# le_grand_strum.net
KiCad netlist of a schematic drawn in EAGLE
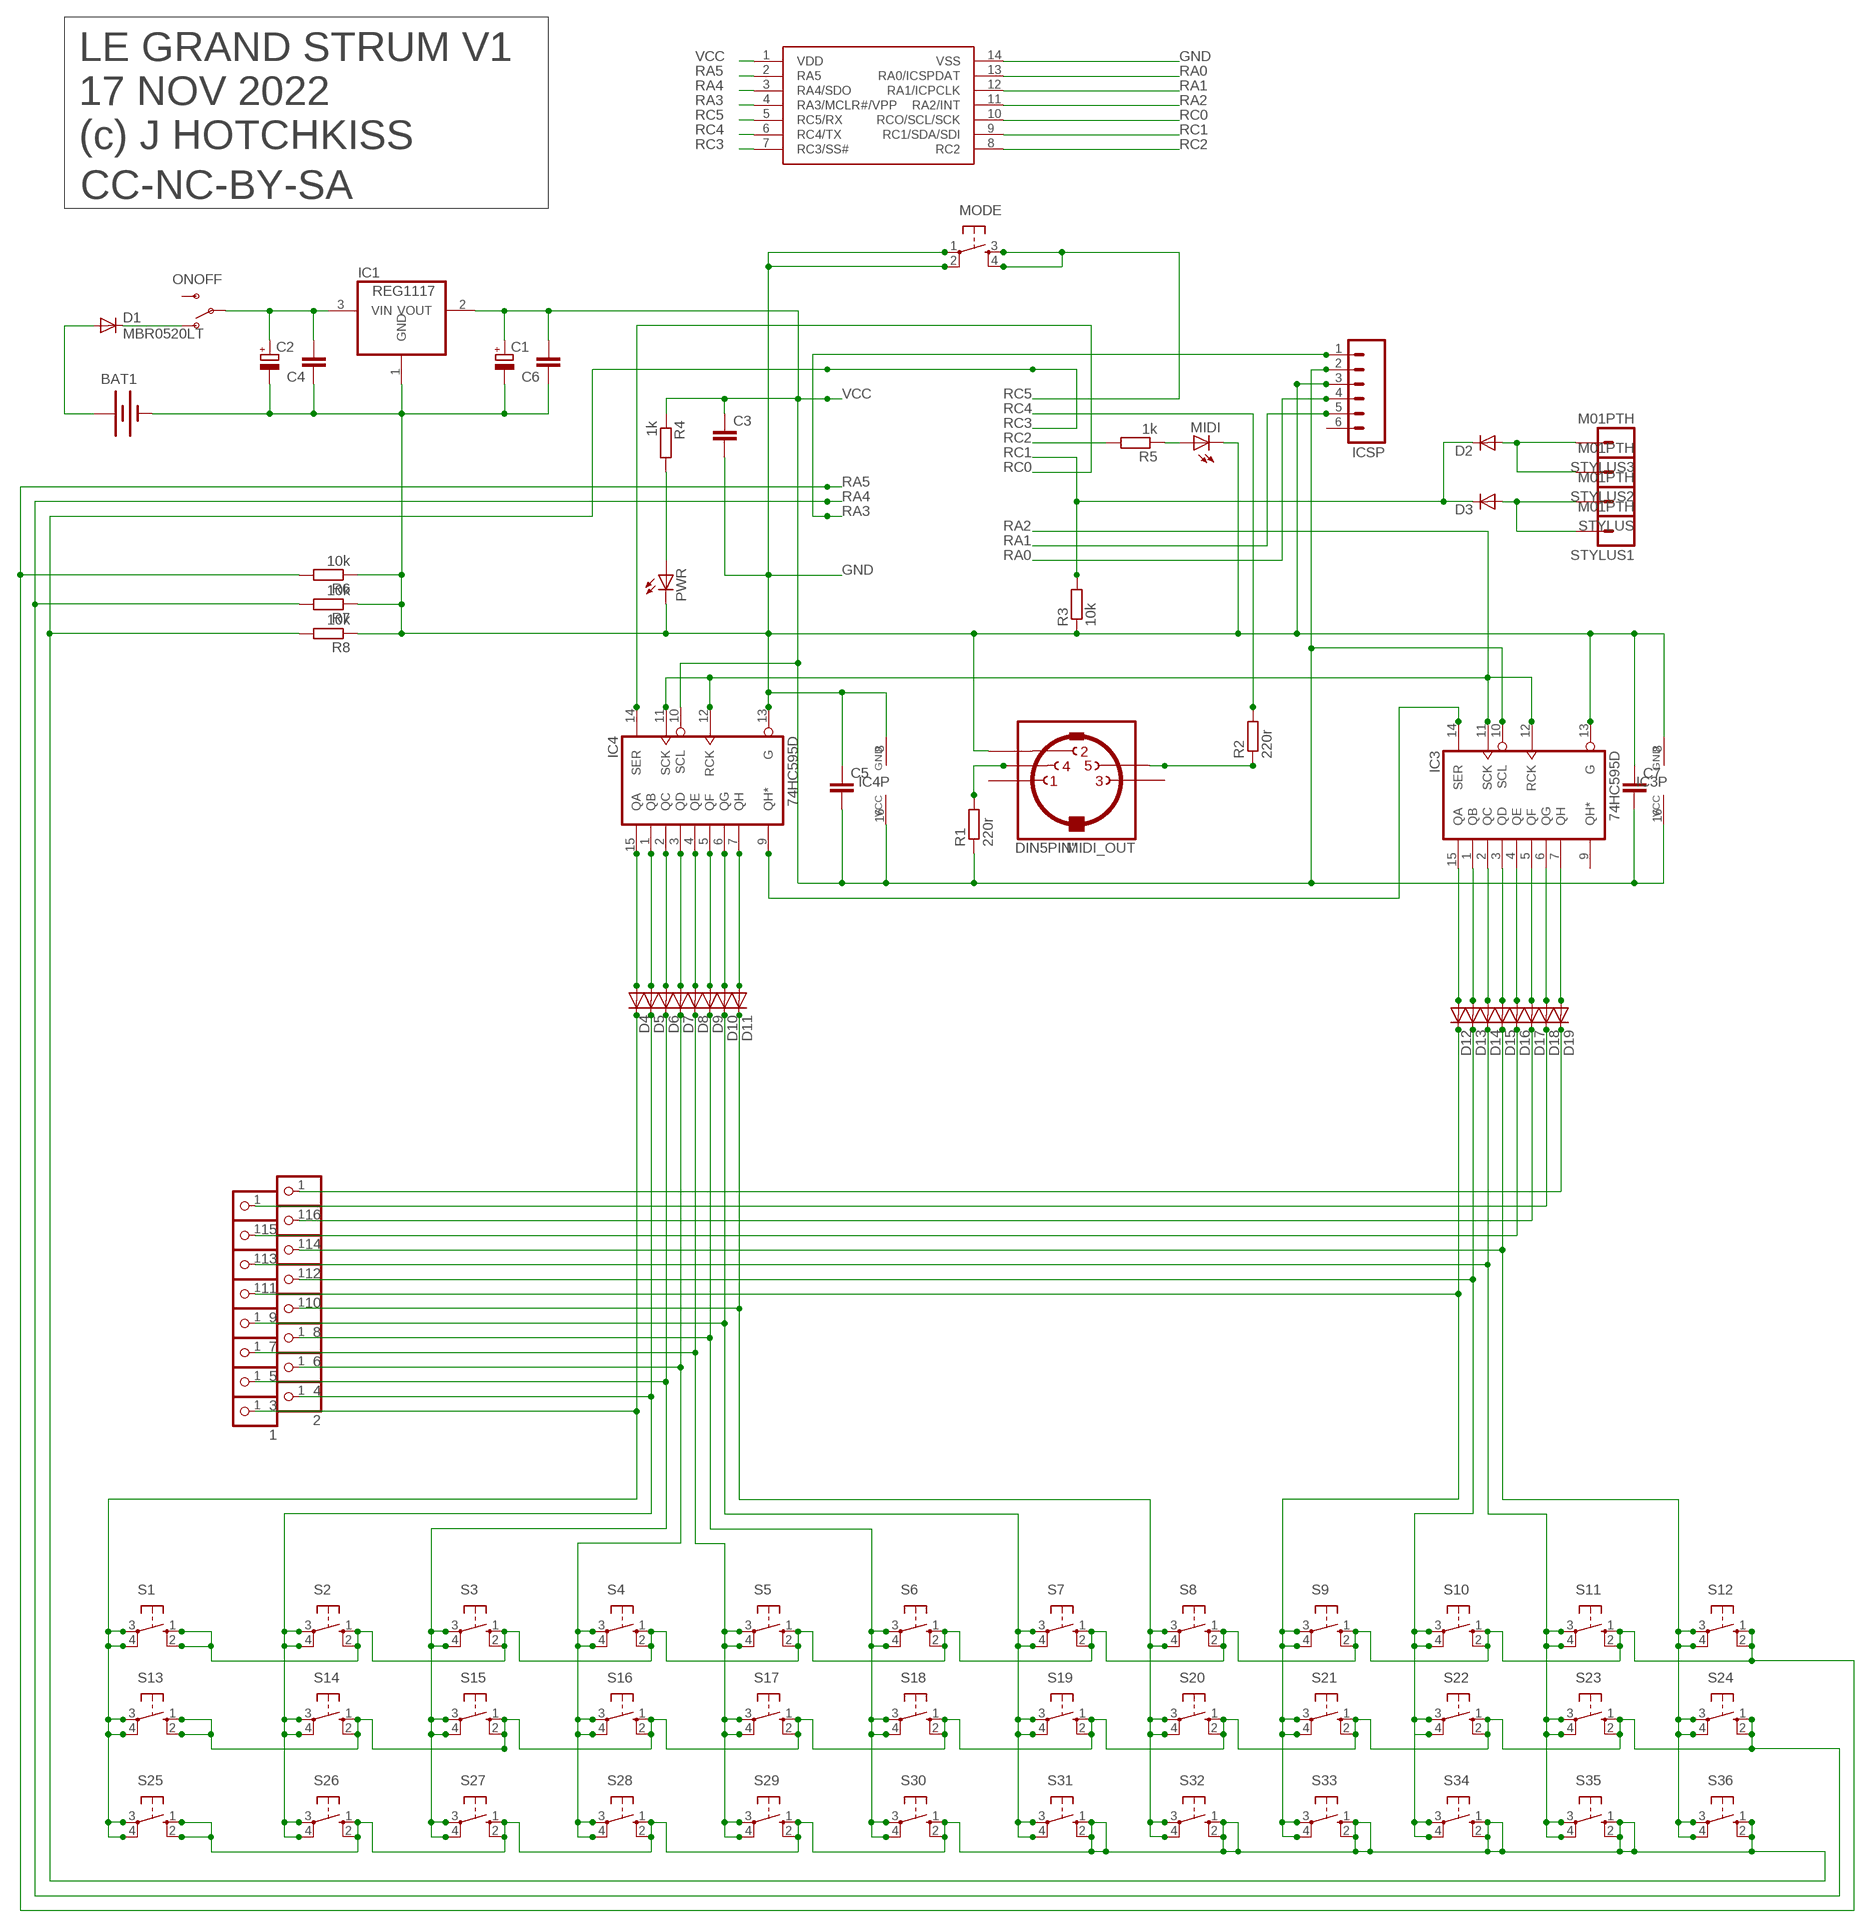
[diagram p0: schematic, sheet 1]

(export (version "E")
  (design (tool "Eeschema 10.0.6"))
  (components
    (comp (ref "1")
      (value "PINHD-1X1")
      (footprint "eagle-import:1X01")
      (libsource (lib "eagle-import") (part "PINHD-1X1"))
    )
    (comp (ref "2")
      (value "PINHD-1X1")
      (footprint "eagle-import:1X01")
      (libsource (lib "eagle-import") (part "PINHD-1X1"))
    )
    (comp (ref "3")
      (value "PINHD-1X1")
      (footprint "eagle-import:1X01")
      (libsource (lib "eagle-import") (part "PINHD-1X1"))
    )
    (comp (ref "4")
      (value "PINHD-1X1")
      (footprint "eagle-import:1X01")
      (libsource (lib "eagle-import") (part "PINHD-1X1"))
    )
    (comp (ref "5")
      (value "PINHD-1X1")
      (footprint "eagle-import:1X01")
      (libsource (lib "eagle-import") (part "PINHD-1X1"))
    )
    (comp (ref "6")
      (value "PINHD-1X1")
      (footprint "eagle-import:1X01")
      (libsource (lib "eagle-import") (part "PINHD-1X1"))
    )
    (comp (ref "7")
      (value "PINHD-1X1")
      (footprint "eagle-import:1X01")
      (libsource (lib "eagle-import") (part "PINHD-1X1"))
    )
    (comp (ref "8")
      (value "PINHD-1X1")
      (footprint "eagle-import:1X01")
      (libsource (lib "eagle-import") (part "PINHD-1X1"))
    )
    (comp (ref "9")
      (value "PINHD-1X1")
      (footprint "eagle-import:1X01")
      (libsource (lib "eagle-import") (part "PINHD-1X1"))
    )
    (comp (ref "10")
      (value "PINHD-1X1")
      (footprint "eagle-import:1X01")
      (libsource (lib "eagle-import") (part "PINHD-1X1"))
    )
    (comp (ref "11")
      (value "PINHD-1X1")
      (footprint "eagle-import:1X01")
      (libsource (lib "eagle-import") (part "PINHD-1X1"))
    )
    (comp (ref "12")
      (value "PINHD-1X1")
      (footprint "eagle-import:1X01")
      (libsource (lib "eagle-import") (part "PINHD-1X1"))
    )
    (comp (ref "13")
      (value "PINHD-1X1")
      (footprint "eagle-import:1X01")
      (libsource (lib "eagle-import") (part "PINHD-1X1"))
    )
    (comp (ref "14")
      (value "PINHD-1X1")
      (footprint "eagle-import:1X01")
      (libsource (lib "eagle-import") (part "PINHD-1X1"))
    )
    (comp (ref "15")
      (value "PINHD-1X1")
      (footprint "eagle-import:1X01")
      (libsource (lib "eagle-import") (part "PINHD-1X1"))
    )
    (comp (ref "16")
      (value "PINHD-1X1")
      (footprint "eagle-import:1X01")
      (libsource (lib "eagle-import") (part "PINHD-1X1"))
    )
    (comp (ref "BAT1")
      (value "BATTERY2HOLES")
      (footprint "eagle-import:PP3_BATTERBOX2")
      (libsource (lib "eagle-import") (part "BATTERY2HOLES"))
    )
    (comp (ref "C1")
      (value "CPOL-EUE2-5")
      (footprint "eagle-import:E2-5")
      (libsource (lib "eagle-import") (part "CPOL-EUE2-5"))
    )
    (comp (ref "C2")
      (value "CPOL-EUE2-5")
      (footprint "eagle-import:E2-5")
      (libsource (lib "eagle-import") (part "CPOL-EUE2-5"))
    )
    (comp (ref "C3")
      (value "C-EUC0805")
      (footprint "eagle-import:C0805")
      (libsource (lib "eagle-import") (part "C-EUC0805"))
    )
    (comp (ref "C4")
      (value "C-EUC0805")
      (footprint "eagle-import:C0805")
      (libsource (lib "eagle-import") (part "C-EUC0805"))
    )
    (comp (ref "C5")
      (value "C-EUC0805")
      (footprint "eagle-import:C0805")
      (libsource (lib "eagle-import") (part "C-EUC0805"))
    )
    (comp (ref "C6")
      (value "C-EUC0805")
      (footprint "eagle-import:C0805")
      (libsource (lib "eagle-import") (part "C-EUC0805"))
    )
    (comp (ref "C7")
      (value "C-EUC0805")
      (footprint "eagle-import:C0805")
      (libsource (lib "eagle-import") (part "C-EUC0805"))
    )
    (comp (ref "D1")
      (value "MBR0520LT")
      (footprint "eagle-import:SOD123")
      (libsource (lib "eagle-import") (part "MBR0520LT"))
    )
    (comp (ref "D2")
      (value "TS4148")
      (footprint "eagle-import:D0805")
      (libsource (lib "eagle-import") (part "TS4148"))
    )
    (comp (ref "D3")
      (value "TS4148")
      (footprint "eagle-import:D0805")
      (libsource (lib "eagle-import") (part "TS4148"))
    )
    (comp (ref "D4")
      (value "TS4148")
      (footprint "eagle-import:D0805")
      (libsource (lib "eagle-import") (part "TS4148"))
    )
    (comp (ref "D5")
      (value "TS4148")
      (footprint "eagle-import:D0805")
      (libsource (lib "eagle-import") (part "TS4148"))
    )
    (comp (ref "D6")
      (value "TS4148")
      (footprint "eagle-import:D0805")
      (libsource (lib "eagle-import") (part "TS4148"))
    )
    (comp (ref "D7")
      (value "TS4148")
      (footprint "eagle-import:D0805")
      (libsource (lib "eagle-import") (part "TS4148"))
    )
    (comp (ref "D8")
      (value "TS4148")
      (footprint "eagle-import:D0805")
      (libsource (lib "eagle-import") (part "TS4148"))
    )
    (comp (ref "D9")
      (value "TS4148")
      (footprint "eagle-import:D0805")
      (libsource (lib "eagle-import") (part "TS4148"))
    )
    (comp (ref "D10")
      (value "TS4148")
      (footprint "eagle-import:D0805")
      (libsource (lib "eagle-import") (part "TS4148"))
    )
    (comp (ref "D11")
      (value "TS4148")
      (footprint "eagle-import:D0805")
      (libsource (lib "eagle-import") (part "TS4148"))
    )
    (comp (ref "D12")
      (value "TS4148")
      (footprint "eagle-import:D0805")
      (libsource (lib "eagle-import") (part "TS4148"))
    )
    (comp (ref "D13")
      (value "TS4148")
      (footprint "eagle-import:D0805")
      (libsource (lib "eagle-import") (part "TS4148"))
    )
    (comp (ref "D14")
      (value "TS4148")
      (footprint "eagle-import:D0805")
      (libsource (lib "eagle-import") (part "TS4148"))
    )
    (comp (ref "D15")
      (value "TS4148")
      (footprint "eagle-import:D0805")
      (libsource (lib "eagle-import") (part "TS4148"))
    )
    (comp (ref "D16")
      (value "TS4148")
      (footprint "eagle-import:D0805")
      (libsource (lib "eagle-import") (part "TS4148"))
    )
    (comp (ref "D17")
      (value "TS4148")
      (footprint "eagle-import:D0805")
      (libsource (lib "eagle-import") (part "TS4148"))
    )
    (comp (ref "D18")
      (value "TS4148")
      (footprint "eagle-import:D0805")
      (libsource (lib "eagle-import") (part "TS4148"))
    )
    (comp (ref "D19")
      (value "TS4148")
      (footprint "eagle-import:D0805")
      (libsource (lib "eagle-import") (part "TS4148"))
    )
    (comp (ref "IC1")
      (value "REG1117")
      (footprint "eagle-import:SOT223")
      (libsource (lib "eagle-import") (part "REG1117"))
    )
    (comp (ref "IC2")
      (value "PIC16F1825SO14")
      (footprint "eagle-import:SO14")
      (libsource (lib "eagle-import") (part "PIC16F1825SO14"))
    )
    (comp (ref "IC3")
      (value "74HC595D")
      (footprint "eagle-import:SO16")
      (libsource (lib "eagle-import") (part "74595DHC"))
    )
    (comp (ref "IC4")
      (value "74HC595D")
      (footprint "eagle-import:SO16")
      (libsource (lib "eagle-import") (part "74595DHC"))
    )
    (comp (ref "ICSP")
      (value "M06SIP")
      (footprint "eagle-import:1X06")
      (libsource (lib "eagle-import") (part "M06SIP"))
    )
    (comp (ref "MIDI")
      (value "LEDCHIPLED_0805")
      (footprint "eagle-import:CHIPLED_0805")
      (libsource (lib "eagle-import") (part "LEDCHIPLED_0805"))
    )
    (comp (ref "MIDI_OUT")
      (value "DIN5PIN\"")
      (footprint "eagle-import:TRUCONN90")
      (libsource (lib "eagle-import") (part "DIN5PIN{dblquote}"))
    )
    (comp (ref "MODE")
      (value "TAC_SWITCHPTH")
      (footprint "eagle-import:TACTILE-PTH")
      (libsource (lib "eagle-import") (part "TAC_SWITCHPTH"))
    )
    (comp (ref "ONOFF")
      (value "SWITCH-SPSTPTH")
      (footprint "eagle-import:SWITCH-SPDT")
      (libsource (lib "eagle-import") (part "SWITCH-SPSTPTH"))
    )
    (comp (ref "PWR")
      (value "LEDCHIPLED_0805")
      (footprint "eagle-import:CHIPLED_0805")
      (libsource (lib "eagle-import") (part "LEDCHIPLED_0805"))
    )
    (comp (ref "R1")
      (value "220r")
      (footprint "eagle-import:R0805")
      (libsource (lib "eagle-import") (part "R-EU_R0805"))
    )
    (comp (ref "R2")
      (value "220r")
      (footprint "eagle-import:R0805")
      (libsource (lib "eagle-import") (part "R-EU_R0805"))
    )
    (comp (ref "R3")
      (value "10k")
      (footprint "eagle-import:R0805")
      (libsource (lib "eagle-import") (part "R-EU_R0805"))
    )
    (comp (ref "R4")
      (value "1k")
      (footprint "eagle-import:R0805")
      (libsource (lib "eagle-import") (part "R-EU_R0805"))
    )
    (comp (ref "R5")
      (value "1k")
      (footprint "eagle-import:R0805")
      (libsource (lib "eagle-import") (part "R-EU_R0805"))
    )
    (comp (ref "R6")
      (value "10k")
      (footprint "eagle-import:R0805")
      (libsource (lib "eagle-import") (part "R-EU_R0805"))
    )
    (comp (ref "R7")
      (value "10k")
      (footprint "eagle-import:R0805")
      (libsource (lib "eagle-import") (part "R-EU_R0805"))
    )
    (comp (ref "R8")
      (value "10k")
      (footprint "eagle-import:R0805")
      (libsource (lib "eagle-import") (part "R-EU_R0805"))
    )
    (comp (ref "S1")
      (value "40-XX")
      (footprint "eagle-import:B3F-40XX")
      (fields (field (name "MF") "OMRON COMPONENTS USA") (field (name "MPN") "B3F-4000"))
      (libsource (lib "eagle-import") (part "40-XX"))
    )
    (comp (ref "S2")
      (value "40-XX")
      (footprint "eagle-import:B3F-40XX")
      (fields (field (name "MF") "OMRON COMPONENTS USA") (field (name "MPN") "B3F-4000"))
      (libsource (lib "eagle-import") (part "40-XX"))
    )
    (comp (ref "S3")
      (value "40-XX")
      (footprint "eagle-import:B3F-40XX")
      (fields (field (name "MF") "OMRON COMPONENTS USA") (field (name "MPN") "B3F-4000"))
      (libsource (lib "eagle-import") (part "40-XX"))
    )
    (comp (ref "S4")
      (value "40-XX")
      (footprint "eagle-import:B3F-40XX")
      (fields (field (name "MF") "OMRON COMPONENTS USA") (field (name "MPN") "B3F-4000"))
      (libsource (lib "eagle-import") (part "40-XX"))
    )
    (comp (ref "S5")
      (value "40-XX")
      (footprint "eagle-import:B3F-40XX")
      (fields (field (name "MF") "OMRON COMPONENTS USA") (field (name "MPN") "B3F-4000"))
      (libsource (lib "eagle-import") (part "40-XX"))
    )
    (comp (ref "S6")
      (value "40-XX")
      (footprint "eagle-import:B3F-40XX")
      (fields (field (name "MF") "OMRON COMPONENTS USA") (field (name "MPN") "B3F-4000"))
      (libsource (lib "eagle-import") (part "40-XX"))
    )
    (comp (ref "S7")
      (value "40-XX")
      (footprint "eagle-import:B3F-40XX")
      (fields (field (name "MF") "OMRON COMPONENTS USA") (field (name "MPN") "B3F-4000"))
      (libsource (lib "eagle-import") (part "40-XX"))
    )
    (comp (ref "S8")
      (value "40-XX")
      (footprint "eagle-import:B3F-40XX")
      (fields (field (name "MF") "OMRON COMPONENTS USA") (field (name "MPN") "B3F-4000"))
      (libsource (lib "eagle-import") (part "40-XX"))
    )
    (comp (ref "S9")
      (value "40-XX")
      (footprint "eagle-import:B3F-40XX")
      (fields (field (name "MF") "OMRON COMPONENTS USA") (field (name "MPN") "B3F-4000"))
      (libsource (lib "eagle-import") (part "40-XX"))
    )
    (comp (ref "S10")
      (value "40-XX")
      (footprint "eagle-import:B3F-40XX")
      (fields (field (name "MF") "OMRON COMPONENTS USA") (field (name "MPN") "B3F-4000"))
      (libsource (lib "eagle-import") (part "40-XX"))
    )
    (comp (ref "S11")
      (value "40-XX")
      (footprint "eagle-import:B3F-40XX")
      (fields (field (name "MF") "OMRON COMPONENTS USA") (field (name "MPN") "B3F-4000"))
      (libsource (lib "eagle-import") (part "40-XX"))
    )
    (comp (ref "S12")
      (value "40-XX")
      (footprint "eagle-import:B3F-40XX")
      (fields (field (name "MF") "OMRON COMPONENTS USA") (field (name "MPN") "B3F-4000"))
      (libsource (lib "eagle-import") (part "40-XX"))
    )
    (comp (ref "S13")
      (value "40-XX")
      (footprint "eagle-import:B3F-40XX")
      (fields (field (name "MF") "OMRON COMPONENTS USA") (field (name "MPN") "B3F-4000"))
      (libsource (lib "eagle-import") (part "40-XX"))
    )
    (comp (ref "S14")
      (value "40-XX")
      (footprint "eagle-import:B3F-40XX")
      (fields (field (name "MF") "OMRON COMPONENTS USA") (field (name "MPN") "B3F-4000"))
      (libsource (lib "eagle-import") (part "40-XX"))
    )
    (comp (ref "S15")
      (value "40-XX")
      (footprint "eagle-import:B3F-40XX")
      (fields (field (name "MF") "OMRON COMPONENTS USA") (field (name "MPN") "B3F-4000"))
      (libsource (lib "eagle-import") (part "40-XX"))
    )
    (comp (ref "S16")
      (value "40-XX")
      (footprint "eagle-import:B3F-40XX")
      (fields (field (name "MF") "OMRON COMPONENTS USA") (field (name "MPN") "B3F-4000"))
      (libsource (lib "eagle-import") (part "40-XX"))
    )
    (comp (ref "S17")
      (value "40-XX")
      (footprint "eagle-import:B3F-40XX")
      (fields (field (name "MF") "OMRON COMPONENTS USA") (field (name "MPN") "B3F-4000"))
      (libsource (lib "eagle-import") (part "40-XX"))
    )
    (comp (ref "S18")
      (value "40-XX")
      (footprint "eagle-import:B3F-40XX")
      (fields (field (name "MF") "OMRON COMPONENTS USA") (field (name "MPN") "B3F-4000"))
      (libsource (lib "eagle-import") (part "40-XX"))
    )
    (comp (ref "S19")
      (value "40-XX")
      (footprint "eagle-import:B3F-40XX")
      (fields (field (name "MF") "OMRON COMPONENTS USA") (field (name "MPN") "B3F-4000"))
      (libsource (lib "eagle-import") (part "40-XX"))
    )
    (comp (ref "S20")
      (value "40-XX")
      (footprint "eagle-import:B3F-40XX")
      (fields (field (name "MF") "OMRON COMPONENTS USA") (field (name "MPN") "B3F-4000"))
      (libsource (lib "eagle-import") (part "40-XX"))
    )
    (comp (ref "S21")
      (value "40-XX")
      (footprint "eagle-import:B3F-40XX")
      (fields (field (name "MF") "OMRON COMPONENTS USA") (field (name "MPN") "B3F-4000"))
      (libsource (lib "eagle-import") (part "40-XX"))
    )
    (comp (ref "S22")
      (value "40-XX")
      (footprint "eagle-import:B3F-40XX")
      (fields (field (name "MF") "OMRON COMPONENTS USA") (field (name "MPN") "B3F-4000"))
      (libsource (lib "eagle-import") (part "40-XX"))
    )
    (comp (ref "S23")
      (value "40-XX")
      (footprint "eagle-import:B3F-40XX")
      (fields (field (name "MF") "OMRON COMPONENTS USA") (field (name "MPN") "B3F-4000"))
      (libsource (lib "eagle-import") (part "40-XX"))
    )
    (comp (ref "S24")
      (value "40-XX")
      (footprint "eagle-import:B3F-40XX")
      (fields (field (name "MF") "OMRON COMPONENTS USA") (field (name "MPN") "B3F-4000"))
      (libsource (lib "eagle-import") (part "40-XX"))
    )
    (comp (ref "S25")
      (value "40-XX")
      (footprint "eagle-import:B3F-40XX")
      (fields (field (name "MF") "OMRON COMPONENTS USA") (field (name "MPN") "B3F-4000"))
      (libsource (lib "eagle-import") (part "40-XX"))
    )
    (comp (ref "S26")
      (value "40-XX")
      (footprint "eagle-import:B3F-40XX")
      (fields (field (name "MF") "OMRON COMPONENTS USA") (field (name "MPN") "B3F-4000"))
      (libsource (lib "eagle-import") (part "40-XX"))
    )
    (comp (ref "S27")
      (value "40-XX")
      (footprint "eagle-import:B3F-40XX")
      (fields (field (name "MF") "OMRON COMPONENTS USA") (field (name "MPN") "B3F-4000"))
      (libsource (lib "eagle-import") (part "40-XX"))
    )
    (comp (ref "S28")
      (value "40-XX")
      (footprint "eagle-import:B3F-40XX")
      (fields (field (name "MF") "OMRON COMPONENTS USA") (field (name "MPN") "B3F-4000"))
      (libsource (lib "eagle-import") (part "40-XX"))
    )
    (comp (ref "S29")
      (value "40-XX")
      (footprint "eagle-import:B3F-40XX")
      (fields (field (name "MF") "OMRON COMPONENTS USA") (field (name "MPN") "B3F-4000"))
      (libsource (lib "eagle-import") (part "40-XX"))
    )
    (comp (ref "S30")
      (value "40-XX")
      (footprint "eagle-import:B3F-40XX")
      (fields (field (name "MF") "OMRON COMPONENTS USA") (field (name "MPN") "B3F-4000"))
      (libsource (lib "eagle-import") (part "40-XX"))
    )
    (comp (ref "S31")
      (value "40-XX")
      (footprint "eagle-import:B3F-40XX")
      (fields (field (name "MF") "OMRON COMPONENTS USA") (field (name "MPN") "B3F-4000"))
      (libsource (lib "eagle-import") (part "40-XX"))
    )
    (comp (ref "S32")
      (value "40-XX")
      (footprint "eagle-import:B3F-40XX")
      (fields (field (name "MF") "OMRON COMPONENTS USA") (field (name "MPN") "B3F-4000"))
      (libsource (lib "eagle-import") (part "40-XX"))
    )
    (comp (ref "S33")
      (value "40-XX")
      (footprint "eagle-import:B3F-40XX")
      (fields (field (name "MF") "OMRON COMPONENTS USA") (field (name "MPN") "B3F-4000"))
      (libsource (lib "eagle-import") (part "40-XX"))
    )
    (comp (ref "S34")
      (value "40-XX")
      (footprint "eagle-import:B3F-40XX")
      (fields (field (name "MF") "OMRON COMPONENTS USA") (field (name "MPN") "B3F-4000"))
      (libsource (lib "eagle-import") (part "40-XX"))
    )
    (comp (ref "S35")
      (value "40-XX")
      (footprint "eagle-import:B3F-40XX")
      (fields (field (name "MF") "OMRON COMPONENTS USA") (field (name "MPN") "B3F-4000"))
      (libsource (lib "eagle-import") (part "40-XX"))
    )
    (comp (ref "S36")
      (value "40-XX")
      (footprint "eagle-import:B3F-40XX")
      (fields (field (name "MF") "OMRON COMPONENTS USA") (field (name "MPN") "B3F-4000"))
      (libsource (lib "eagle-import") (part "40-XX"))
    )
    (comp (ref "STYLUS")
      (value "M01PTH")
      (footprint "eagle-import:1X01")
      (libsource (lib "eagle-import") (part "M01PTH"))
    )
    (comp (ref "STYLUS1")
      (value "M01PTH")
      (footprint "eagle-import:1X01")
      (libsource (lib "eagle-import") (part "M01PTH"))
    )
    (comp (ref "STYLUS2")
      (value "M01PTH")
      (footprint "eagle-import:1X01")
      (libsource (lib "eagle-import") (part "M01PTH"))
    )
    (comp (ref "STYLUS3")
      (value "M01PTH")
      (footprint "eagle-import:1X01")
      (libsource (lib "eagle-import") (part "M01PTH"))
    )
  )
  (nets
    (net (code "1") (name "/GND") (class "Default")
      (node (ref "BAT1") (pin "0V") (pinfunction "-_0V") (pintype "power_in"))
      (node (ref "C1") (pin "-") (pinfunction "-_-") (pintype "passive"))
      (node (ref "C2") (pin "-") (pinfunction "-_-") (pintype "passive"))
      (node (ref "C3") (pin "2") (pinfunction "2_2") (pintype "passive"))
      (node (ref "C4") (pin "1") (pinfunction "1_1") (pintype "passive"))
      (node (ref "C5") (pin "1") (pinfunction "1_1") (pintype "passive"))
      (node (ref "C6") (pin "1") (pinfunction "1_1") (pintype "passive"))
      (node (ref "C7") (pin "1") (pinfunction "1_1") (pintype "passive"))
      (node (ref "IC1") (pin "1") (pinfunction "GND_1") (pintype "power_in"))
      (node (ref "IC2") (pin "14") (pinfunction "VSS_14") (pintype "power_in"))
      (node (ref "IC3") (pin "13") (pinfunction "G_13") (pintype "input"))
      (node (ref "IC3") (pin "8") (pinfunction "GND_8") (pintype "power_in"))
      (node (ref "IC4") (pin "13") (pinfunction "G_13") (pintype "input"))
      (node (ref "IC4") (pin "8") (pinfunction "GND_8") (pintype "power_in"))
      (node (ref "ICSP") (pin "3") (pinfunction "3_3") (pintype "passive"))
      (node (ref "MIDI") (pin "C") (pinfunction "C_C") (pintype "passive"))
      (node (ref "MIDI_OUT") (pin "2") (pinfunction "2_2") (pintype "passive"))
      (node (ref "MODE") (pin "1") (pinfunction "1_1") (pintype "passive"))
      (node (ref "MODE") (pin "2") (pinfunction "2_2") (pintype "passive"))
      (node (ref "PWR") (pin "C") (pinfunction "C_C") (pintype "passive"))
      (node (ref "R3") (pin "1") (pinfunction "1_1") (pintype "passive"))
      (node (ref "R6") (pin "1") (pinfunction "1_1") (pintype "passive"))
      (node (ref "R7") (pin "1") (pinfunction "1_1") (pintype "passive"))
      (node (ref "R8") (pin "1") (pinfunction "1_1") (pintype "passive"))
    )
    (net (code "2") (name "/RA0") (class "Default")
      (node (ref "IC2") (pin "13") (pinfunction "RA0/ICSPDAT_13") (pintype "bidirectional"))
      (node (ref "ICSP") (pin "4") (pinfunction "4_4") (pintype "passive"))
    )
    (net (code "3") (name "/RA1") (class "Default")
      (node (ref "IC2") (pin "12") (pinfunction "RA1/ICPCLK_12") (pintype "bidirectional"))
      (node (ref "ICSP") (pin "5") (pinfunction "5_5") (pintype "passive"))
    )
    (net (code "4") (name "/RA2") (class "Default")
      (node (ref "IC2") (pin "11") (pinfunction "RA2/INT_11") (pintype "bidirectional"))
      (node (ref "IC3") (pin "11") (pinfunction "SCK_11") (pintype "input"))
      (node (ref "IC3") (pin "12") (pinfunction "RCK_12") (pintype "input"))
      (node (ref "IC4") (pin "11") (pinfunction "SCK_11") (pintype "input"))
      (node (ref "IC4") (pin "12") (pinfunction "RCK_12") (pintype "input"))
    )
    (net (code "5") (name "/RA3") (class "Default")
      (node (ref "IC2") (pin "4") (pinfunction "RA3/MCLR#/VPP_4") (pintype "input"))
      (node (ref "ICSP") (pin "1") (pinfunction "1_1") (pintype "passive"))
    )
    (net (code "6") (name "/RA4") (class "Default")
      (node (ref "IC2") (pin "3") (pinfunction "RA4/SDO_3") (pintype "bidirectional"))
      (node (ref "R7") (pin "2") (pinfunction "2_2") (pintype "passive"))
      (node (ref "S13") (pin "1") (pinfunction "S_1") (pintype "passive"))
      (node (ref "S13") (pin "2") (pinfunction "S1_2") (pintype "passive"))
      (node (ref "S14") (pin "1") (pinfunction "S_1") (pintype "passive"))
      (node (ref "S14") (pin "2") (pinfunction "S1_2") (pintype "passive"))
      (node (ref "S15") (pin "1") (pinfunction "S_1") (pintype "passive"))
      (node (ref "S15") (pin "2") (pinfunction "S1_2") (pintype "passive"))
      (node (ref "S16") (pin "1") (pinfunction "S_1") (pintype "passive"))
      (node (ref "S16") (pin "2") (pinfunction "S1_2") (pintype "passive"))
      (node (ref "S17") (pin "1") (pinfunction "S_1") (pintype "passive"))
      (node (ref "S17") (pin "2") (pinfunction "S1_2") (pintype "passive"))
      (node (ref "S18") (pin "1") (pinfunction "S_1") (pintype "passive"))
      (node (ref "S18") (pin "2") (pinfunction "S1_2") (pintype "passive"))
      (node (ref "S19") (pin "1") (pinfunction "S_1") (pintype "passive"))
      (node (ref "S19") (pin "2") (pinfunction "S1_2") (pintype "passive"))
      (node (ref "S20") (pin "1") (pinfunction "S_1") (pintype "passive"))
      (node (ref "S20") (pin "2") (pinfunction "S1_2") (pintype "passive"))
      (node (ref "S21") (pin "1") (pinfunction "S_1") (pintype "passive"))
      (node (ref "S21") (pin "2") (pinfunction "S1_2") (pintype "passive"))
      (node (ref "S22") (pin "1") (pinfunction "S_1") (pintype "passive"))
      (node (ref "S22") (pin "2") (pinfunction "S1_2") (pintype "passive"))
      (node (ref "S23") (pin "1") (pinfunction "S_1") (pintype "passive"))
      (node (ref "S23") (pin "2") (pinfunction "S1_2") (pintype "passive"))
      (node (ref "S24") (pin "1") (pinfunction "S_1") (pintype "passive"))
      (node (ref "S24") (pin "2") (pinfunction "S1_2") (pintype "passive"))
    )
    (net (code "7") (name "/RA5") (class "Default")
      (node (ref "IC2") (pin "2") (pinfunction "RA5_2") (pintype "bidirectional"))
      (node (ref "R6") (pin "2") (pinfunction "2_2") (pintype "passive"))
      (node (ref "S1") (pin "1") (pinfunction "S_1") (pintype "passive"))
      (node (ref "S1") (pin "2") (pinfunction "S1_2") (pintype "passive"))
      (node (ref "S10") (pin "1") (pinfunction "S_1") (pintype "passive"))
      (node (ref "S10") (pin "2") (pinfunction "S1_2") (pintype "passive"))
      (node (ref "S11") (pin "1") (pinfunction "S_1") (pintype "passive"))
      (node (ref "S11") (pin "2") (pinfunction "S1_2") (pintype "passive"))
      (node (ref "S12") (pin "1") (pinfunction "S_1") (pintype "passive"))
      (node (ref "S12") (pin "2") (pinfunction "S1_2") (pintype "passive"))
      (node (ref "S2") (pin "1") (pinfunction "S_1") (pintype "passive"))
      (node (ref "S2") (pin "2") (pinfunction "S1_2") (pintype "passive"))
      (node (ref "S3") (pin "1") (pinfunction "S_1") (pintype "passive"))
      (node (ref "S3") (pin "2") (pinfunction "S1_2") (pintype "passive"))
      (node (ref "S4") (pin "1") (pinfunction "S_1") (pintype "passive"))
      (node (ref "S4") (pin "2") (pinfunction "S1_2") (pintype "passive"))
      (node (ref "S5") (pin "1") (pinfunction "S_1") (pintype "passive"))
      (node (ref "S5") (pin "2") (pinfunction "S1_2") (pintype "passive"))
      (node (ref "S6") (pin "1") (pinfunction "S_1") (pintype "passive"))
      (node (ref "S6") (pin "2") (pinfunction "S1_2") (pintype "passive"))
      (node (ref "S7") (pin "1") (pinfunction "S_1") (pintype "passive"))
      (node (ref "S7") (pin "2") (pinfunction "S1_2") (pintype "passive"))
      (node (ref "S8") (pin "1") (pinfunction "S_1") (pintype "passive"))
      (node (ref "S8") (pin "2") (pinfunction "S1_2") (pintype "passive"))
      (node (ref "S9") (pin "1") (pinfunction "S_1") (pintype "passive"))
      (node (ref "S9") (pin "2") (pinfunction "S1_2") (pintype "passive"))
    )
    (net (code "8") (name "/RC0") (class "Default")
      (node (ref "IC2") (pin "10") (pinfunction "RCO/SCL/SCK_10") (pintype "bidirectional"))
      (node (ref "IC4") (pin "14") (pinfunction "SER_14") (pintype "input"))
    )
    (net (code "9") (name "/RC1") (class "Default")
      (node (ref "D2") (pin "K") (pinfunction "C_K") (pintype "passive"))
      (node (ref "D3") (pin "K") (pinfunction "C_K") (pintype "passive"))
      (node (ref "IC2") (pin "9") (pinfunction "RC1/SDA/SDI_9") (pintype "bidirectional"))
      (node (ref "R3") (pin "2") (pinfunction "2_2") (pintype "passive"))
    )
    (net (code "10") (name "/RC2") (class "Default")
      (node (ref "IC2") (pin "8") (pinfunction "RC2_8") (pintype "bidirectional"))
      (node (ref "R5") (pin "2") (pinfunction "2_2") (pintype "passive"))
    )
    (net (code "11") (name "/RC3") (class "Default")
      (node (ref "IC2") (pin "7") (pinfunction "RC3/SS#_7") (pintype "bidirectional"))
      (node (ref "R8") (pin "2") (pinfunction "2_2") (pintype "passive"))
      (node (ref "S25") (pin "1") (pinfunction "S_1") (pintype "passive"))
      (node (ref "S25") (pin "2") (pinfunction "S1_2") (pintype "passive"))
      (node (ref "S26") (pin "1") (pinfunction "S_1") (pintype "passive"))
      (node (ref "S26") (pin "2") (pinfunction "S1_2") (pintype "passive"))
      (node (ref "S27") (pin "1") (pinfunction "S_1") (pintype "passive"))
      (node (ref "S27") (pin "2") (pinfunction "S1_2") (pintype "passive"))
      (node (ref "S28") (pin "1") (pinfunction "S_1") (pintype "passive"))
      (node (ref "S28") (pin "2") (pinfunction "S1_2") (pintype "passive"))
      (node (ref "S29") (pin "1") (pinfunction "S_1") (pintype "passive"))
      (node (ref "S29") (pin "2") (pinfunction "S1_2") (pintype "passive"))
      (node (ref "S30") (pin "1") (pinfunction "S_1") (pintype "passive"))
      (node (ref "S30") (pin "2") (pinfunction "S1_2") (pintype "passive"))
      (node (ref "S31") (pin "1") (pinfunction "S_1") (pintype "passive"))
      (node (ref "S31") (pin "2") (pinfunction "S1_2") (pintype "passive"))
      (node (ref "S32") (pin "1") (pinfunction "S_1") (pintype "passive"))
      (node (ref "S32") (pin "2") (pinfunction "S1_2") (pintype "passive"))
      (node (ref "S33") (pin "1") (pinfunction "S_1") (pintype "passive"))
      (node (ref "S33") (pin "2") (pinfunction "S1_2") (pintype "passive"))
      (node (ref "S34") (pin "1") (pinfunction "S_1") (pintype "passive"))
      (node (ref "S34") (pin "2") (pinfunction "S1_2") (pintype "passive"))
      (node (ref "S35") (pin "1") (pinfunction "S_1") (pintype "passive"))
      (node (ref "S35") (pin "2") (pinfunction "S1_2") (pintype "passive"))
      (node (ref "S36") (pin "1") (pinfunction "S_1") (pintype "passive"))
      (node (ref "S36") (pin "2") (pinfunction "S1_2") (pintype "passive"))
    )
    (net (code "12") (name "/RC4") (class "Default")
      (node (ref "IC2") (pin "6") (pinfunction "RC4/TX_6") (pintype "bidirectional"))
      (node (ref "R2") (pin "2") (pinfunction "2_2") (pintype "passive"))
    )
    (net (code "13") (name "/RC5") (class "Default")
      (node (ref "IC2") (pin "5") (pinfunction "RC5/RX_5") (pintype "bidirectional"))
      (node (ref "MODE") (pin "3") (pinfunction "3_3") (pintype "passive"))
      (node (ref "MODE") (pin "4") (pinfunction "4_4") (pintype "passive"))
    )
    (net (code "14") (name "/VCC") (class "Default")
      (node (ref "C1") (pin "+") (pinfunction "+_+") (pintype "passive"))
      (node (ref "C3") (pin "1") (pinfunction "1_1") (pintype "passive"))
      (node (ref "C5") (pin "2") (pinfunction "2_2") (pintype "passive"))
      (node (ref "C6") (pin "2") (pinfunction "2_2") (pintype "passive"))
      (node (ref "C7") (pin "2") (pinfunction "2_2") (pintype "passive"))
      (node (ref "IC1") (pin "2") (pinfunction "VOUT_2") (pintype "output"))
      (node (ref "IC2") (pin "1") (pinfunction "VDD_1") (pintype "power_in"))
      (node (ref "IC3") (pin "10") (pinfunction "SCL_10") (pintype "input"))
      (node (ref "IC3") (pin "16") (pinfunction "VCC_16") (pintype "power_in"))
      (node (ref "IC4") (pin "10") (pinfunction "SCL_10") (pintype "input"))
      (node (ref "IC4") (pin "16") (pinfunction "VCC_16") (pintype "power_in"))
      (node (ref "ICSP") (pin "2") (pinfunction "2_2") (pintype "passive"))
      (node (ref "R1") (pin "1") (pinfunction "1_1") (pintype "passive"))
      (node (ref "R4") (pin "1") (pinfunction "1_1") (pintype "passive"))
    )
    (net (code "15") (name "Net-(BAT1-+)") (class "Default")
      (node (ref "BAT1") (pin "9V") (pinfunction "+_9V") (pintype "power_in"))
      (node (ref "D1") (pin "A") (pinfunction "A_A") (pintype "passive"))
    )
    (net (code "16") (name "Net-(D2-PadA)") (class "Default")
      (node (ref "D2") (pin "A") (pinfunction "A_A") (pintype "passive"))
      (node (ref "STYLUS2") (pin "1") (pinfunction "1_1") (pintype "passive"))
      (node (ref "STYLUS3") (pin "1") (pinfunction "1_1") (pintype "passive"))
    )
    (net (code "17") (name "Net-(D3-PadA)") (class "Default")
      (node (ref "D3") (pin "A") (pinfunction "A_A") (pintype "passive"))
      (node (ref "STYLUS") (pin "1") (pinfunction "1_1") (pintype "passive"))
      (node (ref "STYLUS1") (pin "1") (pinfunction "1_1") (pintype "passive"))
    )
    (net (code "18") (name "Net-(D4-C)") (class "Default")
      (node (ref "1") (pin "1") (pinfunction "1_1") (pintype "passive"))
      (node (ref "D4") (pin "K") (pinfunction "C_K") (pintype "passive"))
      (node (ref "S1") (pin "3") (pinfunction "P_3") (pintype "passive"))
      (node (ref "S1") (pin "4") (pinfunction "P1_4") (pintype "passive"))
      (node (ref "S13") (pin "3") (pinfunction "P_3") (pintype "passive"))
      (node (ref "S13") (pin "4") (pinfunction "P1_4") (pintype "passive"))
      (node (ref "S25") (pin "3") (pinfunction "P_3") (pintype "passive"))
      (node (ref "S25") (pin "4") (pinfunction "P1_4") (pintype "passive"))
    )
    (net (code "19") (name "Net-(D5-C)") (class "Default")
      (node (ref "2") (pin "1") (pinfunction "1_1") (pintype "passive"))
      (node (ref "D5") (pin "K") (pinfunction "C_K") (pintype "passive"))
      (node (ref "S14") (pin "3") (pinfunction "P_3") (pintype "passive"))
      (node (ref "S14") (pin "4") (pinfunction "P1_4") (pintype "passive"))
      (node (ref "S2") (pin "3") (pinfunction "P_3") (pintype "passive"))
      (node (ref "S2") (pin "4") (pinfunction "P1_4") (pintype "passive"))
      (node (ref "S26") (pin "3") (pinfunction "P_3") (pintype "passive"))
      (node (ref "S26") (pin "4") (pinfunction "P1_4") (pintype "passive"))
    )
    (net (code "20") (name "Net-(D6-C)") (class "Default")
      (node (ref "3") (pin "1") (pinfunction "1_1") (pintype "passive"))
      (node (ref "D6") (pin "K") (pinfunction "C_K") (pintype "passive"))
      (node (ref "S15") (pin "3") (pinfunction "P_3") (pintype "passive"))
      (node (ref "S15") (pin "4") (pinfunction "P1_4") (pintype "passive"))
      (node (ref "S27") (pin "3") (pinfunction "P_3") (pintype "passive"))
      (node (ref "S27") (pin "4") (pinfunction "P1_4") (pintype "passive"))
      (node (ref "S3") (pin "3") (pinfunction "P_3") (pintype "passive"))
      (node (ref "S3") (pin "4") (pinfunction "P1_4") (pintype "passive"))
    )
    (net (code "21") (name "Net-(D7-C)") (class "Default")
      (node (ref "4") (pin "1") (pinfunction "1_1") (pintype "passive"))
      (node (ref "D7") (pin "K") (pinfunction "C_K") (pintype "passive"))
      (node (ref "S16") (pin "3") (pinfunction "P_3") (pintype "passive"))
      (node (ref "S16") (pin "4") (pinfunction "P1_4") (pintype "passive"))
      (node (ref "S28") (pin "3") (pinfunction "P_3") (pintype "passive"))
      (node (ref "S28") (pin "4") (pinfunction "P1_4") (pintype "passive"))
      (node (ref "S4") (pin "3") (pinfunction "P_3") (pintype "passive"))
      (node (ref "S4") (pin "4") (pinfunction "P1_4") (pintype "passive"))
    )
    (net (code "22") (name "Net-(D8-C)") (class "Default")
      (node (ref "5") (pin "1") (pinfunction "1_1") (pintype "passive"))
      (node (ref "D8") (pin "K") (pinfunction "C_K") (pintype "passive"))
      (node (ref "S17") (pin "3") (pinfunction "P_3") (pintype "passive"))
      (node (ref "S17") (pin "4") (pinfunction "P1_4") (pintype "passive"))
      (node (ref "S29") (pin "3") (pinfunction "P_3") (pintype "passive"))
      (node (ref "S29") (pin "4") (pinfunction "P1_4") (pintype "passive"))
      (node (ref "S5") (pin "3") (pinfunction "P_3") (pintype "passive"))
      (node (ref "S5") (pin "4") (pinfunction "P1_4") (pintype "passive"))
    )
    (net (code "23") (name "Net-(D9-C)") (class "Default")
      (node (ref "6") (pin "1") (pinfunction "1_1") (pintype "passive"))
      (node (ref "D9") (pin "K") (pinfunction "C_K") (pintype "passive"))
      (node (ref "S18") (pin "3") (pinfunction "P_3") (pintype "passive"))
      (node (ref "S18") (pin "4") (pinfunction "P1_4") (pintype "passive"))
      (node (ref "S30") (pin "3") (pinfunction "P_3") (pintype "passive"))
      (node (ref "S30") (pin "4") (pinfunction "P1_4") (pintype "passive"))
      (node (ref "S6") (pin "3") (pinfunction "P_3") (pintype "passive"))
      (node (ref "S6") (pin "4") (pinfunction "P1_4") (pintype "passive"))
    )
    (net (code "24") (name "Net-(D10-C)") (class "Default")
      (node (ref "7") (pin "1") (pinfunction "1_1") (pintype "passive"))
      (node (ref "D10") (pin "K") (pinfunction "C_K") (pintype "passive"))
      (node (ref "S19") (pin "3") (pinfunction "P_3") (pintype "passive"))
      (node (ref "S19") (pin "4") (pinfunction "P1_4") (pintype "passive"))
      (node (ref "S31") (pin "3") (pinfunction "P_3") (pintype "passive"))
      (node (ref "S31") (pin "4") (pinfunction "P1_4") (pintype "passive"))
      (node (ref "S7") (pin "3") (pinfunction "P_3") (pintype "passive"))
      (node (ref "S7") (pin "4") (pinfunction "P1_4") (pintype "passive"))
    )
    (net (code "25") (name "Net-(D11-C)") (class "Default")
      (node (ref "8") (pin "1") (pinfunction "1_1") (pintype "passive"))
      (node (ref "D11") (pin "K") (pinfunction "C_K") (pintype "passive"))
      (node (ref "S20") (pin "3") (pinfunction "P_3") (pintype "passive"))
      (node (ref "S20") (pin "4") (pinfunction "P1_4") (pintype "passive"))
      (node (ref "S32") (pin "3") (pinfunction "P_3") (pintype "passive"))
      (node (ref "S32") (pin "4") (pinfunction "P1_4") (pintype "passive"))
      (node (ref "S8") (pin "3") (pinfunction "P_3") (pintype "passive"))
      (node (ref "S8") (pin "4") (pinfunction "P1_4") (pintype "passive"))
    )
    (net (code "26") (name "Net-(D12-C)") (class "Default")
      (node (ref "9") (pin "1") (pinfunction "1_1") (pintype "passive"))
      (node (ref "D12") (pin "K") (pinfunction "C_K") (pintype "passive"))
      (node (ref "S21") (pin "3") (pinfunction "P_3") (pintype "passive"))
      (node (ref "S21") (pin "4") (pinfunction "P1_4") (pintype "passive"))
      (node (ref "S33") (pin "3") (pinfunction "P_3") (pintype "passive"))
      (node (ref "S33") (pin "4") (pinfunction "P1_4") (pintype "passive"))
      (node (ref "S9") (pin "3") (pinfunction "P_3") (pintype "passive"))
      (node (ref "S9") (pin "4") (pinfunction "P1_4") (pintype "passive"))
    )
    (net (code "27") (name "Net-(D13-C)") (class "Default")
      (node (ref "10") (pin "1") (pinfunction "1_1") (pintype "passive"))
      (node (ref "D13") (pin "K") (pinfunction "C_K") (pintype "passive"))
      (node (ref "S10") (pin "3") (pinfunction "P_3") (pintype "passive"))
      (node (ref "S10") (pin "4") (pinfunction "P1_4") (pintype "passive"))
      (node (ref "S22") (pin "3") (pinfunction "P_3") (pintype "passive"))
      (node (ref "S22") (pin "4") (pinfunction "P1_4") (pintype "passive"))
      (node (ref "S34") (pin "3") (pinfunction "P_3") (pintype "passive"))
      (node (ref "S34") (pin "4") (pinfunction "P1_4") (pintype "passive"))
    )
    (net (code "28") (name "Net-(D14-C)") (class "Default")
      (node (ref "11") (pin "1") (pinfunction "1_1") (pintype "passive"))
      (node (ref "D14") (pin "K") (pinfunction "C_K") (pintype "passive"))
      (node (ref "S11") (pin "3") (pinfunction "P_3") (pintype "passive"))
      (node (ref "S11") (pin "4") (pinfunction "P1_4") (pintype "passive"))
      (node (ref "S23") (pin "3") (pinfunction "P_3") (pintype "passive"))
      (node (ref "S23") (pin "4") (pinfunction "P1_4") (pintype "passive"))
      (node (ref "S35") (pin "3") (pinfunction "P_3") (pintype "passive"))
      (node (ref "S35") (pin "4") (pinfunction "P1_4") (pintype "passive"))
    )
    (net (code "29") (name "Net-(D15-C)") (class "Default")
      (node (ref "12") (pin "1") (pinfunction "1_1") (pintype "passive"))
      (node (ref "D15") (pin "K") (pinfunction "C_K") (pintype "passive"))
      (node (ref "S12") (pin "3") (pinfunction "P_3") (pintype "passive"))
      (node (ref "S12") (pin "4") (pinfunction "P1_4") (pintype "passive"))
      (node (ref "S24") (pin "3") (pinfunction "P_3") (pintype "passive"))
      (node (ref "S24") (pin "4") (pinfunction "P1_4") (pintype "passive"))
      (node (ref "S36") (pin "3") (pinfunction "P_3") (pintype "passive"))
      (node (ref "S36") (pin "4") (pinfunction "P1_4") (pintype "passive"))
    )
    (net (code "30") (name "Net-(D16-C)") (class "Default")
      (node (ref "13") (pin "1") (pinfunction "1_1") (pintype "passive"))
      (node (ref "D16") (pin "K") (pinfunction "C_K") (pintype "passive"))
    )
    (net (code "31") (name "Net-(D17-C)") (class "Default")
      (node (ref "14") (pin "1") (pinfunction "1_1") (pintype "passive"))
      (node (ref "D17") (pin "K") (pinfunction "C_K") (pintype "passive"))
    )
    (net (code "32") (name "Net-(D18-C)") (class "Default")
      (node (ref "15") (pin "1") (pinfunction "1_1") (pintype "passive"))
      (node (ref "D18") (pin "K") (pinfunction "C_K") (pintype "passive"))
    )
    (net (code "33") (name "Net-(D19-C)") (class "Default")
      (node (ref "16") (pin "1") (pinfunction "1_1") (pintype "passive"))
      (node (ref "D19") (pin "K") (pinfunction "C_K") (pintype "passive"))
    )
    (net (code "34") (name "Net-(IC1-VIN)") (class "Default")
      (node (ref "C2") (pin "+") (pinfunction "+_+") (pintype "passive"))
      (node (ref "C4") (pin "2") (pinfunction "2_2") (pintype "passive"))
      (node (ref "IC1") (pin "3") (pinfunction "VIN_3") (pintype "input"))
      (node (ref "ONOFF") (pin "2") (pinfunction "P_2") (pintype "passive"))
    )
    (net (code "35") (name "Net-(IC3A-QA)") (class "Default")
      (node (ref "D12") (pin "A") (pinfunction "A_A") (pintype "passive"))
      (node (ref "IC3") (pin "15") (pinfunction "QA_15") (pintype "tri_state"))
    )
    (net (code "36") (name "Net-(IC3A-QB)") (class "Default")
      (node (ref "D13") (pin "A") (pinfunction "A_A") (pintype "passive"))
      (node (ref "IC3") (pin "1") (pinfunction "QB_1") (pintype "tri_state"))
    )
    (net (code "37") (name "Net-(IC3A-QC)") (class "Default")
      (node (ref "D14") (pin "A") (pinfunction "A_A") (pintype "passive"))
      (node (ref "IC3") (pin "2") (pinfunction "QC_2") (pintype "tri_state"))
    )
    (net (code "38") (name "Net-(IC3A-QD)") (class "Default")
      (node (ref "D15") (pin "A") (pinfunction "A_A") (pintype "passive"))
      (node (ref "IC3") (pin "3") (pinfunction "QD_3") (pintype "tri_state"))
    )
    (net (code "39") (name "Net-(IC3A-QE)") (class "Default")
      (node (ref "D16") (pin "A") (pinfunction "A_A") (pintype "passive"))
      (node (ref "IC3") (pin "4") (pinfunction "QE_4") (pintype "tri_state"))
    )
    (net (code "40") (name "Net-(IC3A-QF)") (class "Default")
      (node (ref "D17") (pin "A") (pinfunction "A_A") (pintype "passive"))
      (node (ref "IC3") (pin "5") (pinfunction "QF_5") (pintype "tri_state"))
    )
    (net (code "41") (name "Net-(IC3A-QG)") (class "Default")
      (node (ref "D18") (pin "A") (pinfunction "A_A") (pintype "passive"))
      (node (ref "IC3") (pin "6") (pinfunction "QG_6") (pintype "tri_state"))
    )
    (net (code "42") (name "Net-(IC3A-QH)") (class "Default")
      (node (ref "D19") (pin "A") (pinfunction "A_A") (pintype "passive"))
      (node (ref "IC3") (pin "7") (pinfunction "QH_7") (pintype "tri_state"))
    )
    (net (code "43") (name "Net-(IC3A-SER)") (class "Default")
      (node (ref "IC3") (pin "14") (pinfunction "SER_14") (pintype "input"))
      (node (ref "IC4") (pin "9") (pinfunction "QH*_9") (pintype "tri_state"))
    )
    (net (code "44") (name "Net-(IC4A-QA)") (class "Default")
      (node (ref "D4") (pin "A") (pinfunction "A_A") (pintype "passive"))
      (node (ref "IC4") (pin "15") (pinfunction "QA_15") (pintype "tri_state"))
    )
    (net (code "45") (name "Net-(IC4A-QB)") (class "Default")
      (node (ref "D5") (pin "A") (pinfunction "A_A") (pintype "passive"))
      (node (ref "IC4") (pin "1") (pinfunction "QB_1") (pintype "tri_state"))
    )
    (net (code "46") (name "Net-(IC4A-QC)") (class "Default")
      (node (ref "D6") (pin "A") (pinfunction "A_A") (pintype "passive"))
      (node (ref "IC4") (pin "2") (pinfunction "QC_2") (pintype "tri_state"))
    )
    (net (code "47") (name "Net-(IC4A-QD)") (class "Default")
      (node (ref "D7") (pin "A") (pinfunction "A_A") (pintype "passive"))
      (node (ref "IC4") (pin "3") (pinfunction "QD_3") (pintype "tri_state"))
    )
    (net (code "48") (name "Net-(IC4A-QE)") (class "Default")
      (node (ref "D8") (pin "A") (pinfunction "A_A") (pintype "passive"))
      (node (ref "IC4") (pin "4") (pinfunction "QE_4") (pintype "tri_state"))
    )
    (net (code "49") (name "Net-(IC4A-QF)") (class "Default")
      (node (ref "D9") (pin "A") (pinfunction "A_A") (pintype "passive"))
      (node (ref "IC4") (pin "5") (pinfunction "QF_5") (pintype "tri_state"))
    )
    (net (code "50") (name "Net-(IC4A-QG)") (class "Default")
      (node (ref "D10") (pin "A") (pinfunction "A_A") (pintype "passive"))
      (node (ref "IC4") (pin "6") (pinfunction "QG_6") (pintype "tri_state"))
    )
    (net (code "51") (name "Net-(IC4A-QH)") (class "Default")
      (node (ref "D11") (pin "A") (pinfunction "A_A") (pintype "passive"))
      (node (ref "IC4") (pin "7") (pinfunction "QH_7") (pintype "tri_state"))
    )
    (net (code "52") (name "Net-(MIDI-PadA)") (class "Default")
      (node (ref "MIDI") (pin "A") (pinfunction "A_A") (pintype "passive"))
      (node (ref "R5") (pin "1") (pinfunction "1_1") (pintype "passive"))
    )
    (net (code "53") (name "Net-(MIDI_OUT-Pad4)") (class "Default")
      (node (ref "MIDI_OUT") (pin "4") (pinfunction "4_4") (pintype "passive"))
      (node (ref "R1") (pin "2") (pinfunction "2_2") (pintype "passive"))
    )
    (net (code "54") (name "Net-(MIDI_OUT-Pad5)") (class "Default")
      (node (ref "MIDI_OUT") (pin "5") (pinfunction "5_5") (pintype "passive"))
      (node (ref "R2") (pin "1") (pinfunction "1_1") (pintype "passive"))
    )
    (net (code "55") (name "Net-(ONOFF-O)") (class "Default")
      (node (ref "D1") (pin "C") (pinfunction "C_C") (pintype "passive"))
      (node (ref "ONOFF") (pin "1") (pinfunction "O_1") (pintype "passive"))
    )
    (net (code "56") (name "Net-(PWR-PadA)") (class "Default")
      (node (ref "PWR") (pin "A") (pinfunction "A_A") (pintype "passive"))
      (node (ref "R4") (pin "2") (pinfunction "2_2") (pintype "passive"))
    )
    (net (code "57") (name "unconnected-(IC3A-QH*-Pad9)") (class "Default")
      (node (ref "IC3") (pin "9") (pinfunction "QH*_9") (pintype "tri_state"))
    )
    (net (code "58") (name "unconnected-(ICSP-Pad6)") (class "Default")
      (node (ref "ICSP") (pin "6") (pinfunction "6_6") (pintype "passive"))
    )
    (net (code "59") (name "unconnected-(MIDI_OUT-Pad1)") (class "Default")
      (node (ref "MIDI_OUT") (pin "1") (pinfunction "1_1") (pintype "passive"))
    )
    (net (code "60") (name "unconnected-(MIDI_OUT-Pad3)") (class "Default")
      (node (ref "MIDI_OUT") (pin "3") (pinfunction "3_3") (pintype "passive"))
    )
    (net (code "61") (name "unconnected-(ONOFF-S-Pad3)") (class "Default")
      (node (ref "ONOFF") (pin "3") (pinfunction "S_3") (pintype "passive"))
    )
  )
)
